# 01_STM32F4.net
KiCad netlist of a schematic drawn in Altium Designer
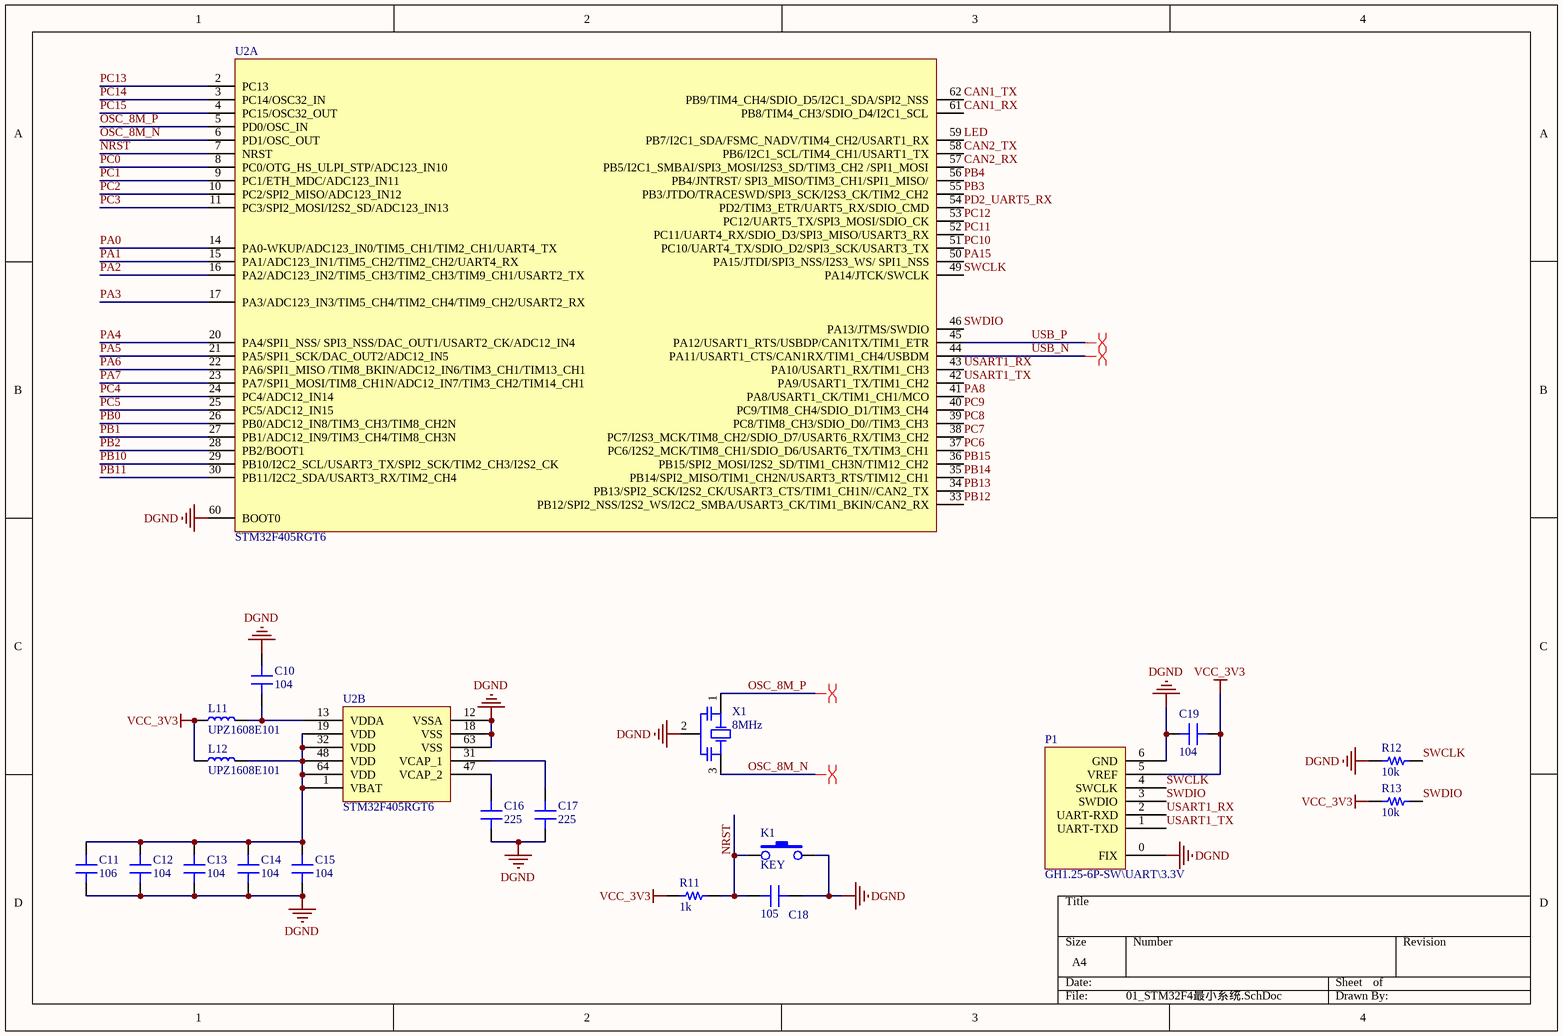
[diagram p0: 01_STM32F4最小系统.SchDoc]

(export (version "E")
  (design (tool "Eeschema 10.0.6"))
  (components
    (comp (ref "C10")
      (value "104")
      (footprint "C0603/1608")
      (description "陶瓷电容")
      (libsource (lib "WMJ2019_Devices") (part "陶瓷电容"))
    )
    (comp (ref "C11")
      (value "106")
      (footprint "C0603/1608")
      (description "陶瓷电容")
      (libsource (lib "WMJ2019_Devices") (part "陶瓷电容"))
    )
    (comp (ref "C12")
      (value "104")
      (footprint "C0603/1608")
      (description "陶瓷电容")
      (libsource (lib "WMJ2019_Devices") (part "陶瓷电容"))
    )
    (comp (ref "C13")
      (value "104")
      (footprint "C0603/1608")
      (description "陶瓷电容")
      (libsource (lib "WMJ2019_Devices") (part "陶瓷电容"))
    )
    (comp (ref "C14")
      (value "104")
      (footprint "C0603/1608")
      (description "陶瓷电容")
      (libsource (lib "WMJ2019_Devices") (part "陶瓷电容"))
    )
    (comp (ref "C15")
      (value "104")
      (footprint "C0603/1608")
      (description "陶瓷电容")
      (libsource (lib "WMJ2019_Devices") (part "陶瓷电容"))
    )
    (comp (ref "C16")
      (value "225")
      (footprint "C0603/1608")
      (description "陶瓷电容")
      (libsource (lib "WMJ2019_Devices") (part "陶瓷电容"))
    )
    (comp (ref "C17")
      (value "225")
      (footprint "C0603/1608")
      (description "陶瓷电容")
      (libsource (lib "WMJ2019_Devices") (part "陶瓷电容"))
    )
    (comp (ref "C18")
      (value "105")
      (footprint "C0603/1608")
      (description "陶瓷电容")
      (libsource (lib "WMJ2019_Devices") (part "陶瓷电容"))
    )
    (comp (ref "C19")
      (value "104")
      (footprint "C0603/1608")
      (description "陶瓷电容")
      (libsource (lib "WMJ2019_Devices") (part "陶瓷电容"))
    )
    (comp (ref "K1")
      (value "KEY")
      (footprint "按键（2脚）")
      (description "按键-2脚贴片")
      (libsource (lib "Devices") (part "按键（2脚）"))
    )
    (comp (ref "L11")
      (value "UPZ1608E101")
      (footprint "L0603/1608")
      (description "贴片磁珠")
      (libsource (lib "WMJ2019_Devices") (part "磁珠"))
    )
    (comp (ref "L12")
      (value "UPZ1608E101")
      (footprint "L0603/1608")
      (description "贴片磁珠")
      (libsource (lib "WMJ2019_Devices") (part "磁珠"))
    )
    (comp (ref "P1")
      (value "GH1.25-6P-S~{W}UAR~{T}3.3V")
      (footprint "GH1.25-6P（卧贴）")
      (description "GH1.25-6P-SW\\UART\\3.3V")
      (libsource (lib "Connectors") (part "GH1.25-6P-SW{backslash}UART{backslash}3.3V"))
    )
    (comp (ref "R11")
      (value "1k")
      (footprint "R0603/1608")
      (description "电阻")
      (libsource (lib "WMJ2019_Devices") (part "电阻"))
    )
    (comp (ref "R12")
      (value "10k")
      (footprint "R0603/1608")
      (description "电阻")
      (libsource (lib "WMJ2019_Devices") (part "电阻"))
    )
    (comp (ref "R13")
      (value "10k")
      (footprint "R0603/1608")
      (description "电阻")
      (libsource (lib "WMJ2019_Devices") (part "电阻"))
    )
    (comp (ref "U2")
      (value "STM32F405RGT6")
      (footprint "LQFP64")
      (description "微控制器STM32F405RGT6")
      (libsource (lib "Devices") (part "STM32F405RGT6"))
    )
    (comp (ref "X1")
      (value "8MHz")
      (footprint "XTAL-3213")
      (description "晶振")
      (libsource (lib "WMJ2019_Devices") (part "晶振（带起振电容）"))
    )
  )
  (nets
    (net (code "1") (name "/CAN1_RX") (class "Default")
      (node (ref "U2") (pin "61") (pinfunction "PB8/TIM4_CH3/SDIO_D4/I2C1_SCL_61") (pintype "passive"))
    )
    (net (code "2") (name "/CAN1_TX") (class "Default")
      (node (ref "U2") (pin "62") (pinfunction "PB9/TIM4_CH4/SDIO_D5/I2C1_SDA/SPI2_NSS_62") (pintype "passive"))
    )
    (net (code "3") (name "/CAN2_RX") (class "Default")
      (node (ref "U2") (pin "57") (pinfunction "PB5/I2C1_SMBAI/SPI3_MOSI/I2S3_SD/TIM3_CH2_/SPI1_MOSI_57") (pintype "passive"))
    )
    (net (code "4") (name "/CAN2_TX") (class "Default")
      (node (ref "U2") (pin "58") (pinfunction "PB6/I2C1_SCL/TIM4_CH1/USART1_TX_58") (pintype "passive"))
    )
    (net (code "5") (name "/LED") (class "Default")
      (node (ref "U2") (pin "59") (pinfunction "PB7/I2C1_SDA/FSMC_NADV/TIM4_CH2/USART1_RX_59") (pintype "passive"))
    )
    (net (code "6") (name "/NRST") (class "Default")
      (node (ref "C18") (pin "2") (pintype "passive"))
      (node (ref "K1") (pin "1") (pintype "passive"))
      (node (ref "R11") (pin "2") (pintype "passive"))
      (node (ref "U2") (pin "7") (pinfunction "NRST_7") (pintype "passive"))
    )
    (net (code "7") (name "/OSC_8M_N") (class "Default")
      (node (ref "U2") (pin "6") (pinfunction "PD1/OSC_OUT_6") (pintype "passive"))
      (node (ref "X1") (pin "3") (pinfunction "OSC3_3") (pintype "passive"))
    )
    (net (code "8") (name "/OSC_8M_P") (class "Default")
      (node (ref "U2") (pin "5") (pinfunction "PD0/OSC_IN_5") (pintype "passive"))
      (node (ref "X1") (pin "1") (pinfunction "OSC1_1") (pintype "passive"))
    )
    (net (code "9") (name "/PA0") (class "Default")
      (node (ref "U2") (pin "14") (pinfunction "PA0-WKUP/ADC123_IN0/TIM5_CH1/TIM2_CH1/UART4_TX_14") (pintype "passive"))
    )
    (net (code "10") (name "/PA1") (class "Default")
      (node (ref "U2") (pin "15") (pinfunction "PA1/ADC123_IN1/TIM5_CH2/TIM2_CH2/UART4_RX_15") (pintype "passive"))
    )
    (net (code "11") (name "/PA2") (class "Default")
      (node (ref "U2") (pin "16") (pinfunction "PA2/ADC123_IN2/TIM5_CH3/TIM2_CH3/TIM9_CH1/USART2_TX_16") (pintype "passive"))
    )
    (net (code "12") (name "/PA3") (class "Default")
      (node (ref "U2") (pin "17") (pinfunction "PA3/ADC123_IN3/TIM5_CH4/TIM2_CH4/TIM9_CH2/USART2_RX_17") (pintype "passive"))
    )
    (net (code "13") (name "/PA4") (class "Default")
      (node (ref "U2") (pin "20") (pinfunction "PA4/SPI1_NSS/_SPI3_NSS/DAC_OUT1/USART2_CK/ADC12_IN4_20") (pintype "passive"))
    )
    (net (code "14") (name "/PA5") (class "Default")
      (node (ref "U2") (pin "21") (pinfunction "PA5/SPI1_SCK/DAC_OUT2/ADC12_IN5_21") (pintype "passive"))
    )
    (net (code "15") (name "/PA6") (class "Default")
      (node (ref "U2") (pin "22") (pinfunction "PA6/SPI1_MISO_/TIM8_BKIN/ADC12_IN6/TIM3_CH1/TIM13_CH1_22") (pintype "passive"))
    )
    (net (code "16") (name "/PA7") (class "Default")
      (node (ref "U2") (pin "23") (pinfunction "PA7/SPI1_MOSI/TIM8_CH1N/ADC12_IN7/TIM3_CH2/TIM14_CH1_23") (pintype "passive"))
    )
    (net (code "17") (name "/PA8") (class "Default")
      (node (ref "U2") (pin "41") (pinfunction "PA8/USART1_CK/TIM1_CH1/MCO_41") (pintype "passive"))
    )
    (net (code "18") (name "/PA15") (class "Default")
      (node (ref "U2") (pin "50") (pinfunction "PA15/JTDI/SPI3_NSS/I2S3_WS/_SPI1_NSS_50") (pintype "passive"))
    )
    (net (code "19") (name "/PB0") (class "Default")
      (node (ref "U2") (pin "26") (pinfunction "PB0/ADC12_IN8/TIM3_CH3/TIM8_CH2N_26") (pintype "passive"))
    )
    (net (code "20") (name "/PB1") (class "Default")
      (node (ref "U2") (pin "27") (pinfunction "PB1/ADC12_IN9/TIM3_CH4/TIM8_CH3N_27") (pintype "passive"))
    )
    (net (code "21") (name "/PB2") (class "Default")
      (node (ref "U2") (pin "28") (pinfunction "PB2/BOOT1_28") (pintype "passive"))
    )
    (net (code "22") (name "/PB3") (class "Default")
      (node (ref "U2") (pin "55") (pinfunction "PB3/JTDO/TRACESWD/SPI3_SCK/I2S3_CK/TIM2_CH2_55") (pintype "passive"))
    )
    (net (code "23") (name "/PB4") (class "Default")
      (node (ref "U2") (pin "56") (pinfunction "PB4/JNTRST/_SPI3_MISO/TIM3_CH1/SPI1_MISO/_56") (pintype "passive"))
    )
    (net (code "24") (name "/PB10") (class "Default")
      (node (ref "U2") (pin "29") (pinfunction "PB10/I2C2_SCL/USART3_TX/SPI2_SCK/TIM2_CH3/I2S2_CK_29") (pintype "passive"))
    )
    (net (code "25") (name "/PB11") (class "Default")
      (node (ref "U2") (pin "30") (pinfunction "PB11/I2C2_SDA/USART3_RX/TIM2_CH4_30") (pintype "passive"))
    )
    (net (code "26") (name "/PB12") (class "Default")
      (node (ref "U2") (pin "33") (pinfunction "PB12/SPI2_NSS/I2S2_WS/I2C2_SMBA/USART3_CK/TIM1_BKIN/CAN2_RX_33") (pintype "passive"))
    )
    (net (code "27") (name "/PB13") (class "Default")
      (node (ref "U2") (pin "34") (pinfunction "PB13/SPI2_SCK/I2S2_CK/USART3_CTS/TIM1_CH1N//CAN2_TX_34") (pintype "passive"))
    )
    (net (code "28") (name "/PB14") (class "Default")
      (node (ref "U2") (pin "35") (pinfunction "PB14/SPI2_MISO/TIM1_CH2N/USART3_RTS/TIM12_CH1_35") (pintype "passive"))
    )
    (net (code "29") (name "/PB15") (class "Default")
      (node (ref "U2") (pin "36") (pinfunction "PB15/SPI2_MOSI/I2S2_SD/TIM1_CH3N/TIM12_CH2_36") (pintype "passive"))
    )
    (net (code "30") (name "/PC0") (class "Default")
      (node (ref "U2") (pin "8") (pinfunction "PC0/OTG_HS_ULPI_STP/ADC123_IN10_8") (pintype "passive"))
    )
    (net (code "31") (name "/PC1") (class "Default")
      (node (ref "U2") (pin "9") (pinfunction "PC1/ETH_MDC/ADC123_IN11_9") (pintype "passive"))
    )
    (net (code "32") (name "/PC2") (class "Default")
      (node (ref "U2") (pin "10") (pinfunction "PC2/SPI2_MISO/ADC123_IN12_10") (pintype "passive"))
    )
    (net (code "33") (name "/PC3") (class "Default")
      (node (ref "U2") (pin "11") (pinfunction "PC3/SPI2_MOSI/I2S2_SD/ADC123_IN13_11") (pintype "passive"))
    )
    (net (code "34") (name "/PC4") (class "Default")
      (node (ref "U2") (pin "24") (pinfunction "PC4/ADC12_IN14_24") (pintype "passive"))
    )
    (net (code "35") (name "/PC5") (class "Default")
      (node (ref "U2") (pin "25") (pinfunction "PC5/ADC12_IN15_25") (pintype "passive"))
    )
    (net (code "36") (name "/PC6") (class "Default")
      (node (ref "U2") (pin "37") (pinfunction "PC6/I2S2_MCK/TIM8_CH1/SDIO_D6/USART6_TX/TIM3_CH1_37") (pintype "passive"))
    )
    (net (code "37") (name "/PC7") (class "Default")
      (node (ref "U2") (pin "38") (pinfunction "PC7/I2S3_MCK/TIM8_CH2/SDIO_D7/USART6_RX/TIM3_CH2_38") (pintype "passive"))
    )
    (net (code "38") (name "/PC8") (class "Default")
      (node (ref "U2") (pin "39") (pinfunction "PC8/TIM8_CH3/SDIO_D0//TIM3_CH3_39") (pintype "passive"))
    )
    (net (code "39") (name "/PC9") (class "Default")
      (node (ref "U2") (pin "40") (pinfunction "PC9/TIM8_CH4/SDIO_D1/TIM3_CH4_40") (pintype "passive"))
    )
    (net (code "40") (name "/PC10") (class "Default")
      (node (ref "U2") (pin "51") (pinfunction "PC10/UART4_TX/SDIO_D2/SPI3_SCK/USART3_TX_51") (pintype "passive"))
    )
    (net (code "41") (name "/PC11") (class "Default")
      (node (ref "U2") (pin "52") (pinfunction "PC11/UART4_RX/SDIO_D3/SPI3_MISO/USART3_RX_52") (pintype "passive"))
    )
    (net (code "42") (name "/PC12") (class "Default")
      (node (ref "U2") (pin "53") (pinfunction "PC12/UART5_TX/SPI3_MOSI/SDIO_CK_53") (pintype "passive"))
    )
    (net (code "43") (name "/PC13") (class "Default")
      (node (ref "U2") (pin "2") (pinfunction "PC13_2") (pintype "passive"))
    )
    (net (code "44") (name "/PC14") (class "Default")
      (node (ref "U2") (pin "3") (pinfunction "PC14/OSC32_IN_3") (pintype "passive"))
    )
    (net (code "45") (name "/PC15") (class "Default")
      (node (ref "U2") (pin "4") (pinfunction "PC15/OSC32_OUT_4") (pintype "passive"))
    )
    (net (code "46") (name "/PD2_UART5_RX") (class "Default")
      (node (ref "U2") (pin "54") (pinfunction "PD2/TIM3_ETR/UART5_RX/SDIO_CMD_54") (pintype "passive"))
    )
    (net (code "47") (name "/SWCLK") (class "Default")
      (node (ref "P1") (pin "4") (pinfunction "SWCLK_4") (pintype "passive"))
      (node (ref "R12") (pin "2") (pintype "passive"))
      (node (ref "U2") (pin "49") (pinfunction "PA14/JTCK/SWCLK_49") (pintype "passive"))
    )
    (net (code "48") (name "/SWDIO") (class "Default")
      (node (ref "P1") (pin "3") (pinfunction "SWDIO_3") (pintype "passive"))
      (node (ref "R13") (pin "2") (pintype "passive"))
      (node (ref "U2") (pin "46") (pinfunction "PA13/JTMS/SWDIO_46") (pintype "passive"))
    )
    (net (code "49") (name "/USART1_RX") (class "Default")
      (node (ref "P1") (pin "2") (pinfunction "UART-RXD_2") (pintype "passive"))
      (node (ref "U2") (pin "43") (pinfunction "PA10/USART1_RX/TIM1_CH3_43") (pintype "passive"))
    )
    (net (code "50") (name "/USART1_TX") (class "Default")
      (node (ref "P1") (pin "1") (pinfunction "UART-TXD_1") (pintype "passive"))
      (node (ref "U2") (pin "42") (pinfunction "PA9/USART1_TX/TIM1_CH2_42") (pintype "passive"))
    )
    (net (code "51") (name "/USB_N") (class "Default")
      (node (ref "U2") (pin "44") (pinfunction "PA11/USART1_CTS/CAN1RX/TIM1_CH4/USBDM_44") (pintype "passive"))
    )
    (net (code "52") (name "/USB_P") (class "Default")
      (node (ref "U2") (pin "45") (pinfunction "PA12/USART1_RTS/USBDP/CAN1TX/TIM1_ETR_45") (pintype "passive"))
    )
    (net (code "53") (name "DGND") (class "Default")
      (node (ref "C10") (pin "2") (pintype "passive"))
      (node (ref "C11") (pin "1") (pintype "passive"))
      (node (ref "C12") (pin "1") (pintype "passive"))
      (node (ref "C13") (pin "1") (pintype "passive"))
      (node (ref "C14") (pin "1") (pintype "passive"))
      (node (ref "C15") (pin "1") (pintype "passive"))
      (node (ref "C16") (pin "1") (pintype "passive"))
      (node (ref "C17") (pin "1") (pintype "passive"))
      (node (ref "C18") (pin "1") (pintype "passive"))
      (node (ref "C19") (pin "2") (pintype "passive"))
      (node (ref "K1") (pin "2") (pintype "passive"))
      (node (ref "P1") (pin "0") (pinfunction "FIX_0") (pintype "passive"))
      (node (ref "P1") (pin "6") (pinfunction "GND_6") (pintype "passive"))
      (node (ref "R12") (pin "1") (pintype "passive"))
      (node (ref "U2") (pin "12") (pinfunction "VSSA_12") (pintype "passive"))
      (node (ref "U2") (pin "18") (pinfunction "VSS_18") (pintype "passive"))
      (node (ref "U2") (pin "60") (pinfunction "BOOT0_60") (pintype "passive"))
      (node (ref "U2") (pin "63") (pinfunction "VSS_63") (pintype "passive"))
      (node (ref "X1") (pin "2") (pinfunction "OSC2_2") (pintype "passive"))
    )
    (net (code "54") (name "Net-(U2B-VBAT)") (class "Default")
      (node (ref "C11") (pin "2") (pintype "passive"))
      (node (ref "C12") (pin "2") (pintype "passive"))
      (node (ref "C13") (pin "2") (pintype "passive"))
      (node (ref "C14") (pin "2") (pintype "passive"))
      (node (ref "C15") (pin "2") (pintype "passive"))
      (node (ref "L12") (pin "2") (pinfunction "2_2") (pintype "passive"))
      (node (ref "U2") (pin "1") (pinfunction "VBAT_1") (pintype "passive"))
      (node (ref "U2") (pin "19") (pinfunction "VDD_19") (pintype "passive"))
      (node (ref "U2") (pin "32") (pinfunction "VDD_32") (pintype "passive"))
      (node (ref "U2") (pin "48") (pinfunction "VDD_48") (pintype "passive"))
      (node (ref "U2") (pin "64") (pinfunction "VDD_64") (pintype "passive"))
    )
    (net (code "55") (name "Net-(U2B-VCAP_1)") (class "Default")
      (node (ref "C17") (pin "2") (pintype "passive"))
      (node (ref "U2") (pin "31") (pinfunction "VCAP_1_31") (pintype "passive"))
    )
    (net (code "56") (name "Net-(U2B-VCAP_2)") (class "Default")
      (node (ref "C16") (pin "2") (pintype "passive"))
      (node (ref "U2") (pin "47") (pinfunction "VCAP_2_47") (pintype "passive"))
    )
    (net (code "57") (name "Net-(U2B-VDDA)") (class "Default")
      (node (ref "C10") (pin "1") (pintype "passive"))
      (node (ref "L11") (pin "2") (pinfunction "2_2") (pintype "passive"))
      (node (ref "U2") (pin "13") (pinfunction "VDDA_13") (pintype "passive"))
    )
    (net (code "58") (name "VCC_3V3") (class "Default")
      (node (ref "C19") (pin "1") (pintype "passive"))
      (node (ref "L11") (pin "1") (pinfunction "1_1") (pintype "passive"))
      (node (ref "L12") (pin "1") (pinfunction "1_1") (pintype "passive"))
      (node (ref "P1") (pin "5") (pinfunction "VREF_5") (pintype "passive"))
      (node (ref "R11") (pin "1") (pintype "passive"))
      (node (ref "R13") (pin "1") (pintype "passive"))
    )
  )
)
